# MesschieberV2.net
KiCad netlist of a schematic drawn in EAGLE
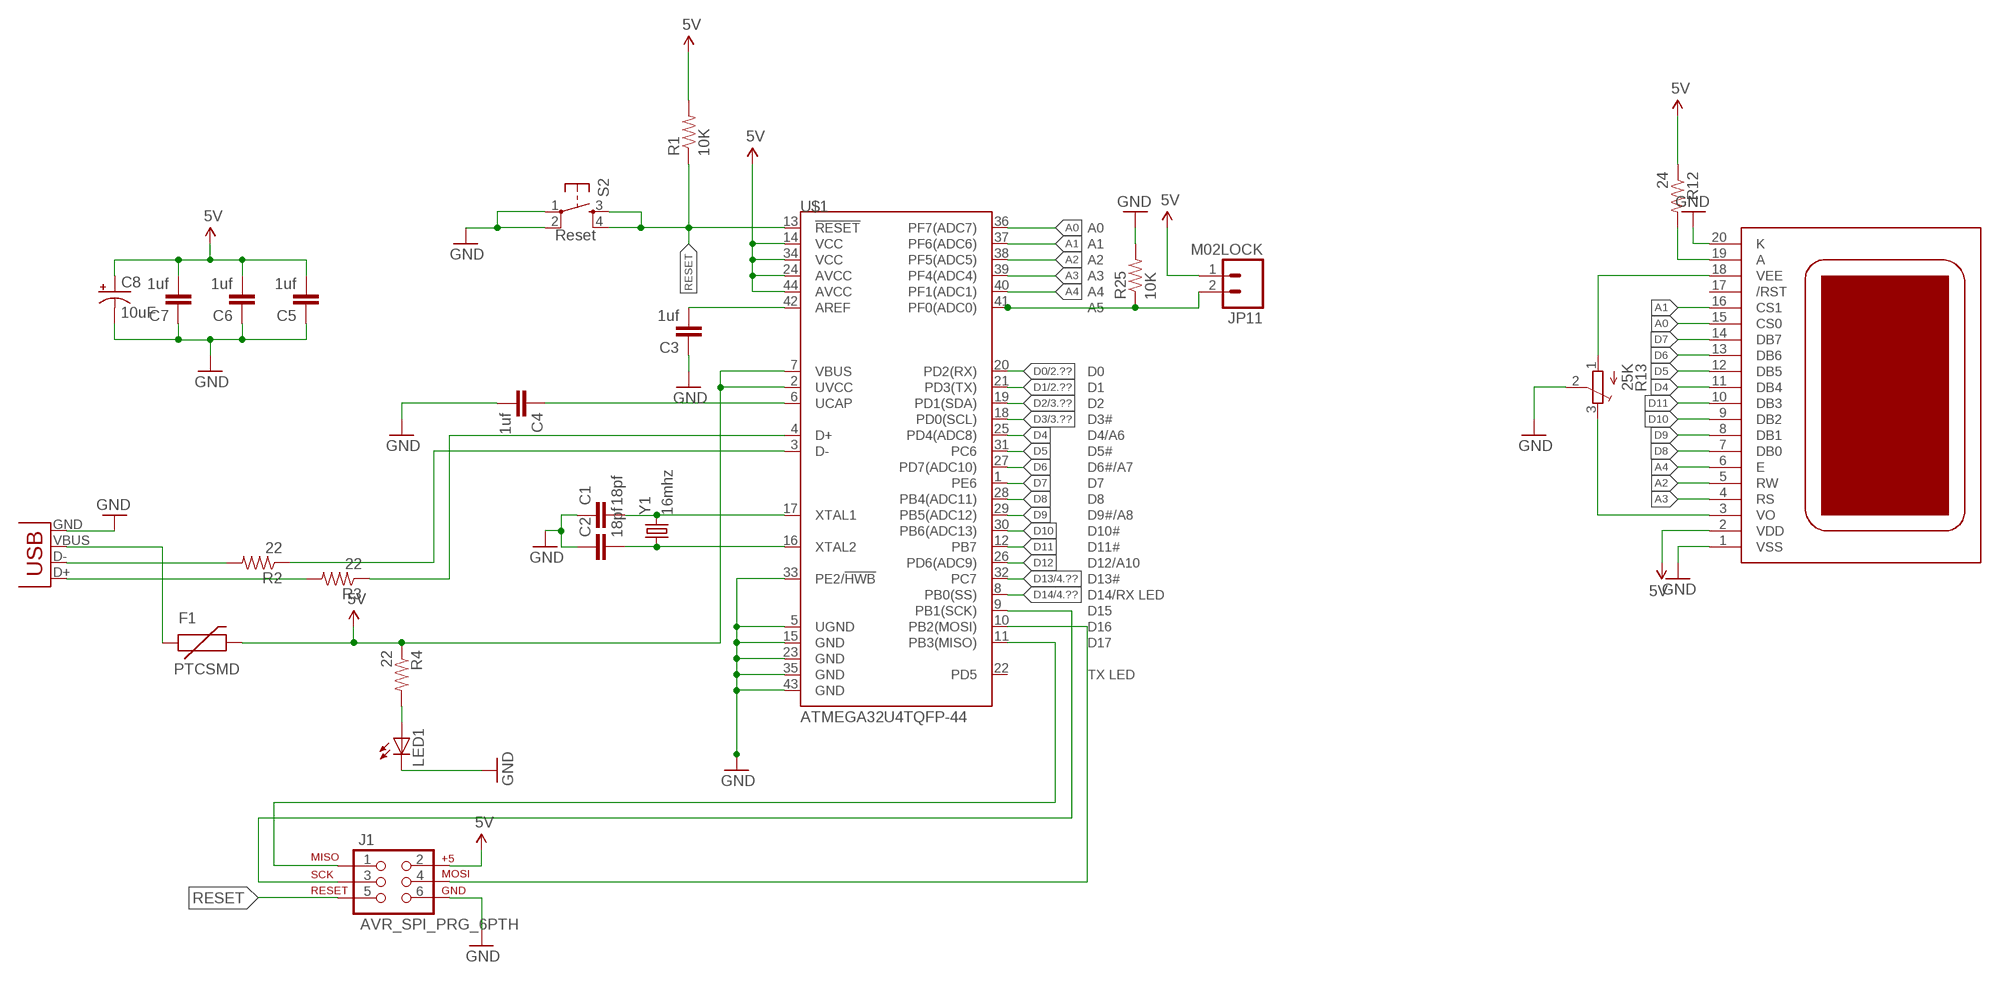
[diagram p0: schematic, sheet 1]
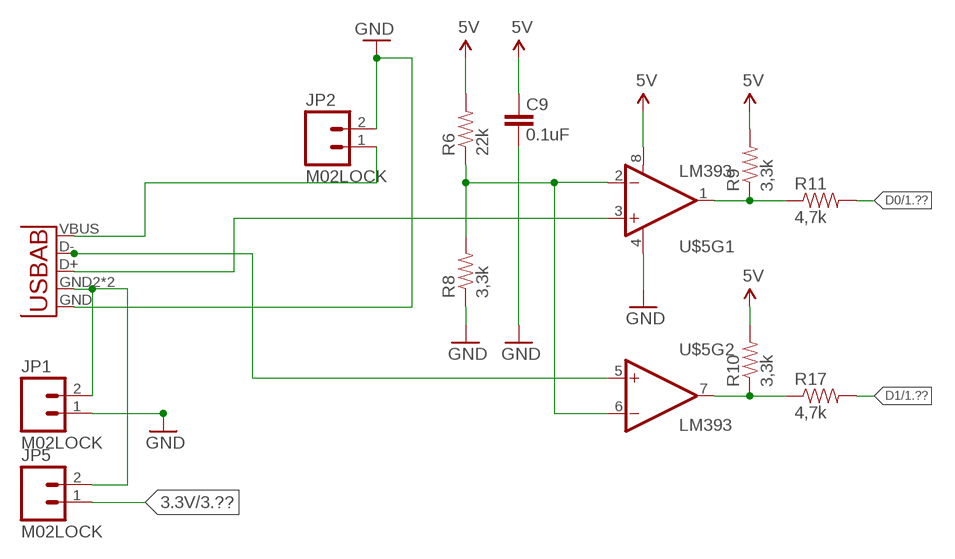
[diagram p1: schematic, sheet 2]
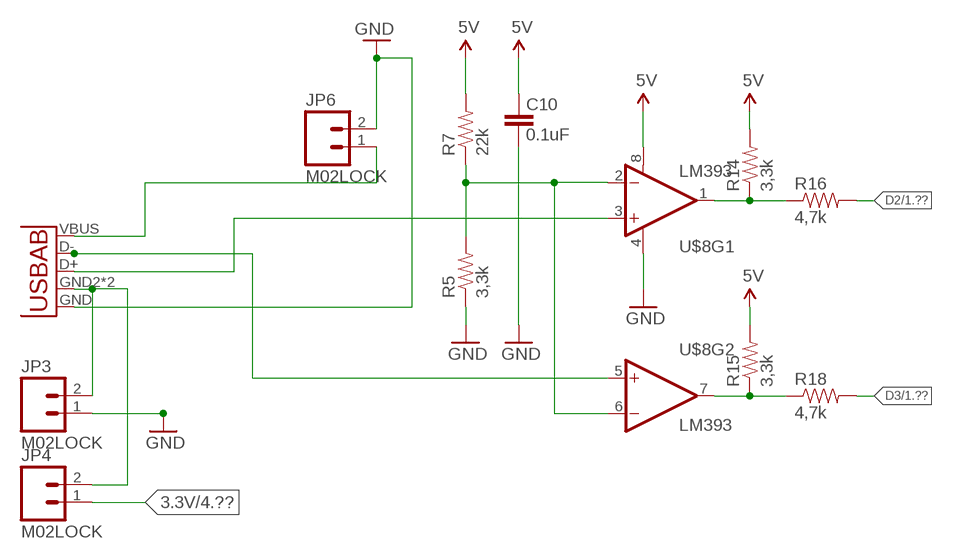
[diagram p2: schematic, sheet 3]
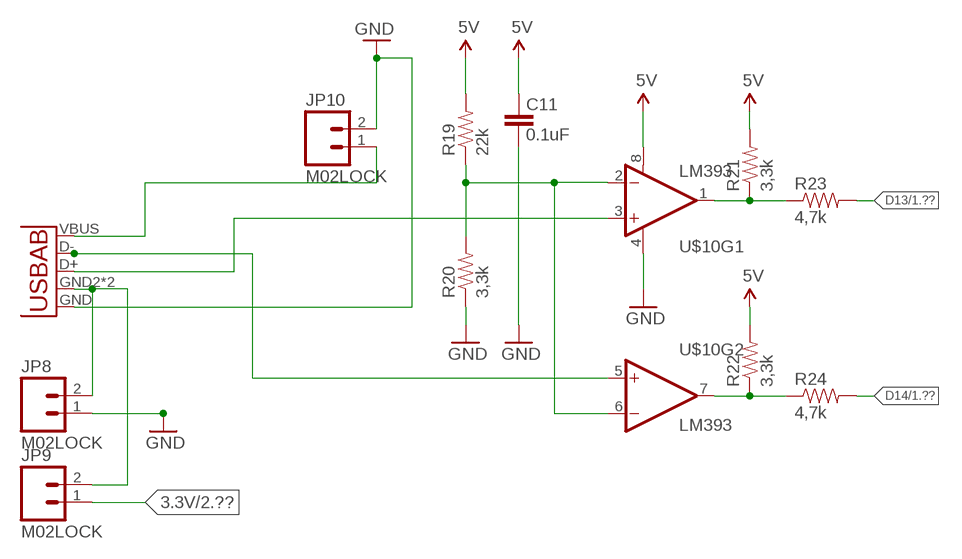
[diagram p3: schematic, sheet 4]

(export (version "E")
  (design (tool "Eeschema 10.0.6"))
  (components
    (comp (ref "C1")
      (value "18pf")
      (footprint "eagle-import:0805")
      (libsource (lib "eagle-import") (part "SparkFun-Capacitors_CAP0805"))
    )
    (comp (ref "C2")
      (value "18pf")
      (footprint "eagle-import:0805")
      (libsource (lib "eagle-import") (part "SparkFun-Capacitors_CAP0805"))
    )
    (comp (ref "C3")
      (value "1uf")
      (footprint "eagle-import:0805")
      (libsource (lib "eagle-import") (part "SparkFun-Capacitors_CAP0805"))
    )
    (comp (ref "C4")
      (value "1uf")
      (footprint "eagle-import:0805")
      (libsource (lib "eagle-import") (part "SparkFun-Capacitors_CAP0805"))
    )
    (comp (ref "C5")
      (value "1uf")
      (footprint "eagle-import:0805")
      (libsource (lib "eagle-import") (part "SparkFun-Capacitors_CAP0805"))
    )
    (comp (ref "C6")
      (value "1uf")
      (footprint "eagle-import:0805")
      (libsource (lib "eagle-import") (part "SparkFun-Capacitors_CAP0805"))
    )
    (comp (ref "C7")
      (value "1uf")
      (footprint "eagle-import:0805")
      (libsource (lib "eagle-import") (part "SparkFun-Capacitors_CAP0805"))
    )
    (comp (ref "C8")
      (value "10uF")
      (footprint "eagle-import:EIA3528")
      (libsource (lib "eagle-import") (part "10UF-20V-10%(TANT)"))
    )
    (comp (ref "F1")
      (value "PTCSMD")
      (footprint "eagle-import:PTC-1206")
      (libsource (lib "eagle-import") (part "PTCSMD"))
    )
    (comp (ref "J1")
      (value "AVR_SPI_PRG_6PTH")
      (footprint "eagle-import:2X3")
      (libsource (lib "eagle-import") (part "AVR_SPI_PRG_6PTH"))
    )
    (comp (ref "JP7")
      (value "USB-SMD-NS")
      (footprint "eagle-import:USB-MINIB-NOSTOP")
      (libsource (lib "eagle-import") (part "USB-SMD-NS"))
    )
    (comp (ref "JP11")
      (value "M02LOCK")
      (footprint "eagle-import:1X02_LOCK")
      (libsource (lib "eagle-import") (part "M02LOCK"))
    )
    (comp (ref "LED1")
      (value "LEDSML0805")
      (footprint "eagle-import:SML0805")
      (libsource (lib "eagle-import") (part "LEDSML0805"))
    )
    (comp (ref "R1")
      (value "10K")
      (footprint "eagle-import:0805")
      (libsource (lib "eagle-import") (part "RESISTOR"))
    )
    (comp (ref "R2")
      (value "22")
      (footprint "eagle-import:0805")
      (libsource (lib "eagle-import") (part "RESISTOR"))
    )
    (comp (ref "R3")
      (value "22")
      (footprint "eagle-import:0805")
      (libsource (lib "eagle-import") (part "RESISTOR"))
    )
    (comp (ref "R4")
      (value "22")
      (footprint "eagle-import:0805")
      (libsource (lib "eagle-import") (part "RESISTOR"))
    )
    (comp (ref "R12")
      (value "24")
      (footprint "eagle-import:0805")
      (libsource (lib "eagle-import") (part "RESISTOR"))
    )
    (comp (ref "R13")
      (value "25K")
      (footprint "eagle-import:SM-42_43A")
      (libsource (lib "eagle-import") (part "TRIM_EU-SM-42/43A"))
    )
    (comp (ref "R25")
      (value "10K")
      (footprint "eagle-import:0805")
      (libsource (lib "eagle-import") (part "RESISTOR"))
    )
    (comp (ref "S2")
      (value "Reset")
      (footprint "eagle-import:TACTILE_SWITCH_SMD")
      (libsource (lib "eagle-import") (part "TAC_SWITCHSND"))
    )
    (comp (ref "U$1")
      (value "ATMEGA32U4TQFP-44")
      (footprint "eagle-import:TQFP44")
      (libsource (lib "eagle-import") (part "ATMEGA32U4TQFP-44"))
    )
    (comp (ref "U$2")
      (value "TS12864A")
      (footprint "eagle-import:TS12864")
      (libsource (lib "eagle-import") (part "TS12864A"))
    )
    (comp (ref "Y1")
      (value "16mhz")
      (footprint "eagle-import:CRYSTAL-SMD-5X3")
      (libsource (lib "eagle-import") (part "CRYSTAL5X3"))
    )
    (comp (ref "C11")
      (value "0.1uF")
      (footprint "eagle-import:0805")
      (libsource (lib "eagle-import") (part "CAP0805"))
    )
    (comp (ref "JP8")
      (value "M02LOCK")
      (footprint "eagle-import:1X02_LOCK")
      (libsource (lib "eagle-import") (part "M02LOCK"))
    )
    (comp (ref "JP9")
      (value "M02LOCK")
      (footprint "eagle-import:1X02_LOCK")
      (libsource (lib "eagle-import") (part "M02LOCK"))
    )
    (comp (ref "JP10")
      (value "M02LOCK")
      (footprint "eagle-import:1X02_LOCK")
      (libsource (lib "eagle-import") (part "M02LOCK"))
    )
    (comp (ref "R19")
      (value "22k")
      (footprint "eagle-import:0805")
      (libsource (lib "eagle-import") (part "RESISTOR"))
    )
    (comp (ref "R20")
      (value "3,3k")
      (footprint "eagle-import:0805")
      (libsource (lib "eagle-import") (part "RESISTOR"))
    )
    (comp (ref "R21")
      (value "3,3k")
      (footprint "eagle-import:0805")
      (libsource (lib "eagle-import") (part "RESISTOR"))
    )
    (comp (ref "R22")
      (value "3,3k")
      (footprint "eagle-import:0805")
      (libsource (lib "eagle-import") (part "RESISTOR"))
    )
    (comp (ref "R23")
      (value "4,7k")
      (footprint "eagle-import:0805")
      (libsource (lib "eagle-import") (part "RESISTOR"))
    )
    (comp (ref "R24")
      (value "4,7k")
      (footprint "eagle-import:0805")
      (libsource (lib "eagle-import") (part "RESISTOR"))
    )
    (comp (ref "U$10")
      (value "LM393")
      (footprint "eagle-import:SO08")
      (libsource (lib "eagle-import") (part "LM393"))
    )
    (comp (ref "U$11")
      (value "USB-A")
      (footprint "eagle-import:USB-A")
      (libsource (lib "eagle-import") (part "USB-A"))
    )
    (comp (ref "C10")
      (value "0.1uF")
      (footprint "eagle-import:0805")
      (libsource (lib "eagle-import") (part "CAP0805"))
    )
    (comp (ref "JP3")
      (value "M02LOCK")
      (footprint "eagle-import:1X02_LOCK")
      (libsource (lib "eagle-import") (part "M02LOCK"))
    )
    (comp (ref "JP4")
      (value "M02LOCK")
      (footprint "eagle-import:1X02_LOCK")
      (libsource (lib "eagle-import") (part "M02LOCK"))
    )
    (comp (ref "JP6")
      (value "M02LOCK")
      (footprint "eagle-import:1X02_LOCK")
      (libsource (lib "eagle-import") (part "M02LOCK"))
    )
    (comp (ref "R5")
      (value "3,3k")
      (footprint "eagle-import:0805")
      (libsource (lib "eagle-import") (part "RESISTOR"))
    )
    (comp (ref "R7")
      (value "22k")
      (footprint "eagle-import:0805")
      (libsource (lib "eagle-import") (part "RESISTOR"))
    )
    (comp (ref "R14")
      (value "3,3k")
      (footprint "eagle-import:0805")
      (libsource (lib "eagle-import") (part "RESISTOR"))
    )
    (comp (ref "R15")
      (value "3,3k")
      (footprint "eagle-import:0805")
      (libsource (lib "eagle-import") (part "RESISTOR"))
    )
    (comp (ref "R16")
      (value "4,7k")
      (footprint "eagle-import:0805")
      (libsource (lib "eagle-import") (part "RESISTOR"))
    )
    (comp (ref "R18")
      (value "4,7k")
      (footprint "eagle-import:0805")
      (libsource (lib "eagle-import") (part "RESISTOR"))
    )
    (comp (ref "U$8")
      (value "LM393")
      (footprint "eagle-import:SO08")
      (libsource (lib "eagle-import") (part "LM393"))
    )
    (comp (ref "U$9")
      (value "USB-A")
      (footprint "eagle-import:USB-A")
      (libsource (lib "eagle-import") (part "USB-A"))
    )
    (comp (ref "C9")
      (value "0.1uF")
      (footprint "eagle-import:0805")
      (libsource (lib "eagle-import") (part "CAP0805"))
    )
    (comp (ref "JP1")
      (value "M02LOCK")
      (footprint "eagle-import:1X02_LOCK")
      (libsource (lib "eagle-import") (part "M02LOCK"))
    )
    (comp (ref "JP2")
      (value "M02LOCK")
      (footprint "eagle-import:1X02_LOCK")
      (libsource (lib "eagle-import") (part "M02LOCK"))
    )
    (comp (ref "JP5")
      (value "M02LOCK")
      (footprint "eagle-import:1X02_LOCK")
      (libsource (lib "eagle-import") (part "M02LOCK"))
    )
    (comp (ref "R6")
      (value "22k")
      (footprint "eagle-import:0805")
      (libsource (lib "eagle-import") (part "RESISTOR"))
    )
    (comp (ref "R8")
      (value "3,3k")
      (footprint "eagle-import:0805")
      (libsource (lib "eagle-import") (part "RESISTOR"))
    )
    (comp (ref "R9")
      (value "3,3k")
      (footprint "eagle-import:0805")
      (libsource (lib "eagle-import") (part "RESISTOR"))
    )
    (comp (ref "R10")
      (value "3,3k")
      (footprint "eagle-import:0805")
      (libsource (lib "eagle-import") (part "RESISTOR"))
    )
    (comp (ref "R11")
      (value "4,7k")
      (footprint "eagle-import:0805")
      (libsource (lib "eagle-import") (part "RESISTOR"))
    )
    (comp (ref "R17")
      (value "4,7k")
      (footprint "eagle-import:0805")
      (libsource (lib "eagle-import") (part "RESISTOR"))
    )
    (comp (ref "U$5")
      (value "LM393")
      (footprint "eagle-import:SO08")
      (libsource (lib "eagle-import") (part "LM393"))
    )
    (comp (ref "U$7")
      (value "USB-A")
      (footprint "eagle-import:USB-A")
      (libsource (lib "eagle-import") (part "USB-A"))
    )
  )
  (nets
    (net (code "1") (name "3.3V") (class "Default")
      (node (ref "JP4") (pin "1") (pinfunction "1_1") (pintype "passive"))
      (node (ref "JP5") (pin "1") (pinfunction "1_1") (pintype "passive"))
      (node (ref "JP9") (pin "1") (pinfunction "1_1") (pintype "passive"))
    )
    (net (code "2") (name "5V") (class "Default")
      (node (ref "C10") (pin "2") (pinfunction "2_2") (pintype "passive"))
      (node (ref "C11") (pin "2") (pinfunction "2_2") (pintype "passive"))
      (node (ref "C5") (pin "2") (pinfunction "2_2") (pintype "passive"))
      (node (ref "C6") (pin "2") (pinfunction "2_2") (pintype "passive"))
      (node (ref "C7") (pin "2") (pinfunction "2_2") (pintype "passive"))
      (node (ref "C8") (pin "A") (pinfunction "+_A") (pintype "passive"))
      (node (ref "C9") (pin "2") (pinfunction "2_2") (pintype "passive"))
      (node (ref "F1") (pin "2") (pinfunction "2_2") (pintype "bidirectional"))
      (node (ref "J1") (pin "2") (pinfunction "2_2") (pintype "passive"))
      (node (ref "JP11") (pin "1") (pinfunction "1_1") (pintype "passive"))
      (node (ref "R1") (pin "2") (pinfunction "2_2") (pintype "passive"))
      (node (ref "R10") (pin "2") (pinfunction "2_2") (pintype "passive"))
      (node (ref "R12") (pin "1") (pinfunction "1_1") (pintype "passive"))
      (node (ref "R14") (pin "2") (pinfunction "2_2") (pintype "passive"))
      (node (ref "R15") (pin "2") (pinfunction "2_2") (pintype "passive"))
      (node (ref "R19") (pin "2") (pinfunction "2_2") (pintype "passive"))
      (node (ref "R21") (pin "2") (pinfunction "2_2") (pintype "passive"))
      (node (ref "R22") (pin "2") (pinfunction "2_2") (pintype "passive"))
      (node (ref "R4") (pin "1") (pinfunction "1_1") (pintype "passive"))
      (node (ref "R6") (pin "2") (pinfunction "2_2") (pintype "passive"))
      (node (ref "R7") (pin "2") (pinfunction "2_2") (pintype "passive"))
      (node (ref "R9") (pin "2") (pinfunction "2_2") (pintype "passive"))
      (node (ref "U$1") (pin "14") (pinfunction "VCC_14") (pintype "bidirectional"))
      (node (ref "U$1") (pin "2") (pinfunction "UVCC_2") (pintype "bidirectional"))
      (node (ref "U$1") (pin "24") (pinfunction "AVCC_24") (pintype "bidirectional"))
      (node (ref "U$1") (pin "34") (pinfunction "VCC_34") (pintype "bidirectional"))
      (node (ref "U$1") (pin "44") (pinfunction "AVCC_44") (pintype "bidirectional"))
      (node (ref "U$1") (pin "7") (pinfunction "VBUS_7") (pintype "bidirectional"))
      (node (ref "U$10") (pin "8") (pinfunction "V+_8") (pintype "power_in"))
      (node (ref "U$2") (pin "2") (pinfunction "VDD_2") (pintype "power_in"))
      (node (ref "U$5") (pin "8") (pinfunction "V+_8") (pintype "power_in"))
      (node (ref "U$8") (pin "8") (pinfunction "V+_8") (pintype "power_in"))
    )
    (net (code "3") (name "A0") (class "Default")
      (node (ref "U$1") (pin "36") (pinfunction "PF7(ADC7)_36") (pintype "bidirectional"))
      (node (ref "U$2") (pin "15") (pinfunction "CS0_15") (pintype "input"))
    )
    (net (code "4") (name "A1") (class "Default")
      (node (ref "U$1") (pin "37") (pinfunction "PF6(ADC6)_37") (pintype "bidirectional"))
      (node (ref "U$2") (pin "16") (pinfunction "CS1_16") (pintype "input"))
    )
    (net (code "5") (name "A2") (class "Default")
      (node (ref "U$1") (pin "38") (pinfunction "PF5(ADC5)_38") (pintype "bidirectional"))
      (node (ref "U$2") (pin "5") (pinfunction "RW_5") (pintype "input"))
    )
    (net (code "6") (name "A3") (class "Default")
      (node (ref "U$1") (pin "39") (pinfunction "PF4(ADC4)_39") (pintype "bidirectional"))
      (node (ref "U$2") (pin "4") (pinfunction "RS_4") (pintype "input"))
    )
    (net (code "7") (name "A4") (class "Default")
      (node (ref "U$1") (pin "40") (pinfunction "PF1(ADC1)_40") (pintype "bidirectional"))
      (node (ref "U$2") (pin "6") (pinfunction "E_6") (pintype "input"))
    )
    (net (code "8") (name "D0") (class "Default")
      (node (ref "R11") (pin "2") (pinfunction "2_2") (pintype "passive"))
      (node (ref "U$1") (pin "20") (pinfunction "PD2(RX)_20") (pintype "bidirectional"))
    )
    (net (code "9") (name "D1") (class "Default")
      (node (ref "R17") (pin "2") (pinfunction "2_2") (pintype "passive"))
      (node (ref "U$1") (pin "21") (pinfunction "PD3(TX)_21") (pintype "bidirectional"))
    )
    (net (code "10") (name "D2") (class "Default")
      (node (ref "R16") (pin "2") (pinfunction "2_2") (pintype "passive"))
      (node (ref "U$1") (pin "19") (pinfunction "PD1(SDA)_19") (pintype "bidirectional"))
    )
    (net (code "11") (name "D3") (class "Default")
      (node (ref "R18") (pin "2") (pinfunction "2_2") (pintype "passive"))
      (node (ref "U$1") (pin "18") (pinfunction "PD0(SCL)_18") (pintype "bidirectional"))
    )
    (net (code "12") (name "D4") (class "Default")
      (node (ref "U$1") (pin "25") (pinfunction "PD4(ADC8)_25") (pintype "bidirectional"))
      (node (ref "U$2") (pin "11") (pinfunction "DB4_11") (pintype "bidirectional"))
    )
    (net (code "13") (name "D5") (class "Default")
      (node (ref "U$1") (pin "31") (pinfunction "PC6_31") (pintype "bidirectional"))
      (node (ref "U$2") (pin "12") (pinfunction "DB5_12") (pintype "bidirectional"))
    )
    (net (code "14") (name "D6") (class "Default")
      (node (ref "U$1") (pin "27") (pinfunction "PD7(ADC10)_27") (pintype "bidirectional"))
      (node (ref "U$2") (pin "13") (pinfunction "DB6_13") (pintype "bidirectional"))
    )
    (net (code "15") (name "D7") (class "Default")
      (node (ref "U$1") (pin "1") (pinfunction "PE6_1") (pintype "bidirectional"))
      (node (ref "U$2") (pin "14") (pinfunction "DB7_14") (pintype "bidirectional"))
    )
    (net (code "16") (name "D8") (class "Default")
      (node (ref "U$1") (pin "28") (pinfunction "PB4(ADC11)_28") (pintype "bidirectional"))
      (node (ref "U$2") (pin "7") (pinfunction "DB0_7") (pintype "bidirectional"))
    )
    (net (code "17") (name "D9") (class "Default")
      (node (ref "U$1") (pin "29") (pinfunction "PB5(ADC12)_29") (pintype "bidirectional"))
      (node (ref "U$2") (pin "8") (pinfunction "DB1_8") (pintype "bidirectional"))
    )
    (net (code "18") (name "D10") (class "Default")
      (node (ref "U$1") (pin "30") (pinfunction "PB6(ADC13)_30") (pintype "bidirectional"))
      (node (ref "U$2") (pin "9") (pinfunction "DB2_9") (pintype "bidirectional"))
    )
    (net (code "19") (name "D11") (class "Default")
      (node (ref "U$1") (pin "12") (pinfunction "PB7_12") (pintype "bidirectional"))
      (node (ref "U$2") (pin "10") (pinfunction "DB3_10") (pintype "bidirectional"))
    )
    (net (code "20") (name "D12") (class "Default")
      (node (ref "U$1") (pin "26") (pinfunction "PD6(ADC9)_26") (pintype "bidirectional"))
    )
    (net (code "21") (name "D13") (class "Default")
      (node (ref "R23") (pin "2") (pinfunction "2_2") (pintype "passive"))
      (node (ref "U$1") (pin "32") (pinfunction "PC7_32") (pintype "bidirectional"))
    )
    (net (code "22") (name "D14") (class "Default")
      (node (ref "R24") (pin "2") (pinfunction "2_2") (pintype "passive"))
      (node (ref "U$1") (pin "8") (pinfunction "PB0(SS)_8") (pintype "bidirectional"))
    )
    (net (code "23") (name "GND") (class "Default")
      (node (ref "C1") (pin "1") (pinfunction "1_1") (pintype "passive"))
      (node (ref "C10") (pin "1") (pinfunction "1_1") (pintype "passive"))
      (node (ref "C11") (pin "1") (pinfunction "1_1") (pintype "passive"))
      (node (ref "C2") (pin "1") (pinfunction "1_1") (pintype "passive"))
      (node (ref "C3") (pin "1") (pinfunction "1_1") (pintype "passive"))
      (node (ref "C4") (pin "2") (pinfunction "2_2") (pintype "passive"))
      (node (ref "C5") (pin "1") (pinfunction "1_1") (pintype "passive"))
      (node (ref "C6") (pin "1") (pinfunction "1_1") (pintype "passive"))
      (node (ref "C7") (pin "1") (pinfunction "1_1") (pintype "passive"))
      (node (ref "C8") (pin "C") (pinfunction "-_C") (pintype "passive"))
      (node (ref "C9") (pin "1") (pinfunction "1_1") (pintype "passive"))
      (node (ref "J1") (pin "6") (pinfunction "6_6") (pintype "passive"))
      (node (ref "JP1") (pin "1") (pinfunction "1_1") (pintype "passive"))
      (node (ref "JP10") (pin "2") (pinfunction "2_2") (pintype "passive"))
      (node (ref "JP2") (pin "2") (pinfunction "2_2") (pintype "passive"))
      (node (ref "JP3") (pin "1") (pinfunction "1_1") (pintype "passive"))
      (node (ref "JP6") (pin "2") (pinfunction "2_2") (pintype "passive"))
      (node (ref "JP7") (pin "GND") (pinfunction "GND_GND") (pintype "bidirectional"))
      (node (ref "JP8") (pin "1") (pinfunction "1_1") (pintype "passive"))
      (node (ref "LED1") (pin "C") (pinfunction "C_C") (pintype "passive"))
      (node (ref "R13") (pin "2") (pinfunction "S_2") (pintype "passive"))
      (node (ref "R20") (pin "1") (pinfunction "1_1") (pintype "passive"))
      (node (ref "R25") (pin "2") (pinfunction "2_2") (pintype "passive"))
      (node (ref "R5") (pin "1") (pinfunction "1_1") (pintype "passive"))
      (node (ref "R8") (pin "1") (pinfunction "1_1") (pintype "passive"))
      (node (ref "S2") (pin "1") (pinfunction "1_1") (pintype "passive"))
      (node (ref "S2") (pin "2") (pinfunction "2_2") (pintype "passive"))
      (node (ref "U$1") (pin "15") (pinfunction "GND_15") (pintype "bidirectional"))
      (node (ref "U$1") (pin "23") (pinfunction "GND_23") (pintype "bidirectional"))
      (node (ref "U$1") (pin "33") (pinfunction "PE2/~{HWB}_33") (pintype "bidirectional"))
      (node (ref "U$1") (pin "35") (pinfunction "GND_35") (pintype "bidirectional"))
      (node (ref "U$1") (pin "43") (pinfunction "GND_43") (pintype "bidirectional"))
      (node (ref "U$1") (pin "5") (pinfunction "UGND_5") (pintype "bidirectional"))
      (node (ref "U$10") (pin "4") (pinfunction "V-_4") (pintype "power_in"))
      (node (ref "U$11") (pin "GND") (pinfunction "GND_GND") (pintype "bidirectional"))
      (node (ref "U$2") (pin "1") (pinfunction "VSS_1") (pintype "power_in"))
      (node (ref "U$2") (pin "20") (pinfunction "K_20") (pintype "input"))
      (node (ref "U$5") (pin "4") (pinfunction "V-_4") (pintype "power_in"))
      (node (ref "U$7") (pin "GND") (pinfunction "GND_GND") (pintype "bidirectional"))
      (node (ref "U$8") (pin "4") (pinfunction "V-_4") (pintype "power_in"))
      (node (ref "U$9") (pin "GND") (pinfunction "GND_GND") (pintype "bidirectional"))
    )
    (net (code "24") (name "Net-(F1-Pad1)") (class "Default")
      (node (ref "F1") (pin "1") (pinfunction "1_1") (pintype "bidirectional"))
      (node (ref "JP7") (pin "VBUS") (pinfunction "VBUS_VBUS") (pintype "bidirectional"))
    )
    (net (code "25") (name "Net-(JP1-Pad2)") (class "Default")
      (node (ref "JP1") (pin "2") (pinfunction "2_2") (pintype "passive"))
      (node (ref "JP5") (pin "2") (pinfunction "2_2") (pintype "passive"))
      (node (ref "U$7") (pin "GND2") (pinfunction "USBID_GND2") (pintype "bidirectional"))
      (node (ref "U$7") (pin "GND3") (pinfunction "USBID_GND3") (pintype "bidirectional"))
    )
    (net (code "26") (name "Net-(JP2-Pad1)") (class "Default")
      (node (ref "JP2") (pin "1") (pinfunction "1_1") (pintype "passive"))
      (node (ref "U$7") (pin "VBUS") (pinfunction "VBUS_VBUS") (pintype "bidirectional"))
    )
    (net (code "27") (name "Net-(JP3-Pad2)") (class "Default")
      (node (ref "JP3") (pin "2") (pinfunction "2_2") (pintype "passive"))
      (node (ref "JP4") (pin "2") (pinfunction "2_2") (pintype "passive"))
      (node (ref "U$9") (pin "GND2") (pinfunction "USBID_GND2") (pintype "bidirectional"))
      (node (ref "U$9") (pin "GND3") (pinfunction "USBID_GND3") (pintype "bidirectional"))
    )
    (net (code "28") (name "Net-(JP6-Pad1)") (class "Default")
      (node (ref "JP6") (pin "1") (pinfunction "1_1") (pintype "passive"))
      (node (ref "U$9") (pin "VBUS") (pinfunction "VBUS_VBUS") (pintype "bidirectional"))
    )
    (net (code "29") (name "Net-(JP7-PadD+)") (class "Default")
      (node (ref "JP7") (pin "D+") (pinfunction "D+_D+") (pintype "bidirectional"))
      (node (ref "R3") (pin "2") (pinfunction "2_2") (pintype "passive"))
    )
    (net (code "30") (name "Net-(JP7-PadD-)") (class "Default")
      (node (ref "JP7") (pin "D-") (pinfunction "D-_D-") (pintype "bidirectional"))
      (node (ref "R2") (pin "2") (pinfunction "2_2") (pintype "passive"))
    )
    (net (code "31") (name "Net-(JP8-Pad2)") (class "Default")
      (node (ref "JP8") (pin "2") (pinfunction "2_2") (pintype "passive"))
      (node (ref "JP9") (pin "2") (pinfunction "2_2") (pintype "passive"))
      (node (ref "U$11") (pin "GND2") (pinfunction "USBID_GND2") (pintype "bidirectional"))
      (node (ref "U$11") (pin "GND3") (pinfunction "USBID_GND3") (pintype "bidirectional"))
    )
    (net (code "32") (name "Net-(JP10-Pad1)") (class "Default")
      (node (ref "JP10") (pin "1") (pinfunction "1_1") (pintype "passive"))
      (node (ref "U$11") (pin "VBUS") (pinfunction "VBUS_VBUS") (pintype "bidirectional"))
    )
    (net (code "33") (name "Net-(LED1-PadA)") (class "Default")
      (node (ref "LED1") (pin "A") (pinfunction "A_A") (pintype "passive"))
      (node (ref "R4") (pin "2") (pinfunction "2_2") (pintype "passive"))
    )
    (net (code "34") (name "Net-(R13-A)") (class "Default")
      (node (ref "R13") (pin "1") (pinfunction "A_1") (pintype "passive"))
      (node (ref "U$2") (pin "18") (pinfunction "VEE_18") (pintype "power_in"))
    )
    (net (code "35") (name "Net-(R13-E)") (class "Default")
      (node (ref "R13") (pin "3") (pinfunction "E_3") (pintype "passive"))
      (node (ref "U$2") (pin "3") (pinfunction "VO_3") (pintype "input"))
    )
    (net (code "36") (name "Net-(U$1-AREF)") (class "Default")
      (node (ref "C3") (pin "2") (pinfunction "2_2") (pintype "passive"))
      (node (ref "U$1") (pin "42") (pinfunction "AREF_42") (pintype "bidirectional"))
    )
    (net (code "37") (name "Net-(U$1-D+)") (class "Default")
      (node (ref "R3") (pin "1") (pinfunction "1_1") (pintype "passive"))
      (node (ref "U$1") (pin "4") (pinfunction "D+_4") (pintype "bidirectional"))
    )
    (net (code "38") (name "Net-(U$1-D-)") (class "Default")
      (node (ref "R2") (pin "1") (pinfunction "1_1") (pintype "passive"))
      (node (ref "U$1") (pin "3") (pinfunction "D-_3") (pintype "bidirectional"))
    )
    (net (code "39") (name "Net-(U$1-PB1(SCK))") (class "Default")
      (node (ref "J1") (pin "3") (pinfunction "3_3") (pintype "passive"))
      (node (ref "U$1") (pin "9") (pinfunction "PB1(SCK)_9") (pintype "bidirectional"))
    )
    (net (code "40") (name "Net-(U$1-PB2(MOSI))") (class "Default")
      (node (ref "J1") (pin "4") (pinfunction "4_4") (pintype "passive"))
      (node (ref "U$1") (pin "10") (pinfunction "PB2(MOSI)_10") (pintype "bidirectional"))
    )
    (net (code "41") (name "Net-(U$1-PB3(MISO))") (class "Default")
      (node (ref "J1") (pin "1") (pinfunction "1_1") (pintype "passive"))
      (node (ref "U$1") (pin "11") (pinfunction "PB3(MISO)_11") (pintype "bidirectional"))
    )
    (net (code "42") (name "Net-(U$1-PF0(ADC0))") (class "Default")
      (node (ref "JP11") (pin "2") (pinfunction "2_2") (pintype "passive"))
      (node (ref "R25") (pin "1") (pinfunction "1_1") (pintype "passive"))
      (node (ref "U$1") (pin "41") (pinfunction "PF0(ADC0)_41") (pintype "bidirectional"))
    )
    (net (code "43") (name "Net-(U$1-UCAP)") (class "Default")
      (node (ref "C4") (pin "1") (pinfunction "1_1") (pintype "passive"))
      (node (ref "U$1") (pin "6") (pinfunction "UCAP_6") (pintype "bidirectional"))
    )
    (net (code "44") (name "Net-(U$1-XTAL1)") (class "Default")
      (node (ref "C1") (pin "2") (pinfunction "2_2") (pintype "passive"))
      (node (ref "U$1") (pin "17") (pinfunction "XTAL1_17") (pintype "bidirectional"))
      (node (ref "Y1") (pin "3") (pinfunction "2_3") (pintype "passive"))
    )
    (net (code "45") (name "Net-(U$1-XTAL2)") (class "Default")
      (node (ref "C2") (pin "2") (pinfunction "2_2") (pintype "passive"))
      (node (ref "U$1") (pin "16") (pinfunction "XTAL2_16") (pintype "bidirectional"))
      (node (ref "Y1") (pin "1") (pinfunction "1_1") (pintype "passive"))
    )
    (net (code "46") (name "Net-(U$2-A)") (class "Default")
      (node (ref "R12") (pin "2") (pinfunction "2_2") (pintype "passive"))
      (node (ref "U$2") (pin "19") (pinfunction "A_19") (pintype "power_in"))
    )
    (net (code "47") (name "Net-(U$5A-+IN)") (class "Default")
      (node (ref "U$5") (pin "3") (pinfunction "+IN_3") (pintype "input"))
      (node (ref "U$7") (pin "D+") (pinfunction "D+_D+") (pintype "bidirectional"))
    )
    (net (code "48") (name "Net-(U$5A--IN)") (class "Default")
      (node (ref "R6") (pin "1") (pinfunction "1_1") (pintype "passive"))
      (node (ref "R8") (pin "2") (pinfunction "2_2") (pintype "passive"))
      (node (ref "U$5") (pin "2") (pinfunction "-IN_2") (pintype "input"))
      (node (ref "U$5") (pin "6") (pinfunction "-IN_6") (pintype "input"))
    )
    (net (code "49") (name "Net-(U$5A-OUT)") (class "Default")
      (node (ref "R11") (pin "1") (pinfunction "1_1") (pintype "passive"))
      (node (ref "R9") (pin "1") (pinfunction "1_1") (pintype "passive"))
      (node (ref "U$5") (pin "1") (pinfunction "OUT_1") (pintype "output"))
    )
    (net (code "50") (name "Net-(U$5B-+IN)") (class "Default")
      (node (ref "U$5") (pin "5") (pinfunction "+IN_5") (pintype "input"))
      (node (ref "U$7") (pin "D-") (pinfunction "D-_D-") (pintype "bidirectional"))
    )
    (net (code "51") (name "Net-(U$5B-OUT)") (class "Default")
      (node (ref "R10") (pin "1") (pinfunction "1_1") (pintype "passive"))
      (node (ref "R17") (pin "1") (pinfunction "1_1") (pintype "passive"))
      (node (ref "U$5") (pin "7") (pinfunction "OUT_7") (pintype "output"))
    )
    (net (code "52") (name "Net-(U$8A-+IN)") (class "Default")
      (node (ref "U$8") (pin "3") (pinfunction "+IN_3") (pintype "input"))
      (node (ref "U$9") (pin "D+") (pinfunction "D+_D+") (pintype "bidirectional"))
    )
    (net (code "53") (name "Net-(U$8A--IN)") (class "Default")
      (node (ref "R5") (pin "2") (pinfunction "2_2") (pintype "passive"))
      (node (ref "R7") (pin "1") (pinfunction "1_1") (pintype "passive"))
      (node (ref "U$8") (pin "2") (pinfunction "-IN_2") (pintype "input"))
      (node (ref "U$8") (pin "6") (pinfunction "-IN_6") (pintype "input"))
    )
    (net (code "54") (name "Net-(U$8A-OUT)") (class "Default")
      (node (ref "R14") (pin "1") (pinfunction "1_1") (pintype "passive"))
      (node (ref "R16") (pin "1") (pinfunction "1_1") (pintype "passive"))
      (node (ref "U$8") (pin "1") (pinfunction "OUT_1") (pintype "output"))
    )
    (net (code "55") (name "Net-(U$8B-+IN)") (class "Default")
      (node (ref "U$8") (pin "5") (pinfunction "+IN_5") (pintype "input"))
      (node (ref "U$9") (pin "D-") (pinfunction "D-_D-") (pintype "bidirectional"))
    )
    (net (code "56") (name "Net-(U$8B-OUT)") (class "Default")
      (node (ref "R15") (pin "1") (pinfunction "1_1") (pintype "passive"))
      (node (ref "R18") (pin "1") (pinfunction "1_1") (pintype "passive"))
      (node (ref "U$8") (pin "7") (pinfunction "OUT_7") (pintype "output"))
    )
    (net (code "57") (name "Net-(U$10A-+IN)") (class "Default")
      (node (ref "U$10") (pin "3") (pinfunction "+IN_3") (pintype "input"))
      (node (ref "U$11") (pin "D+") (pinfunction "D+_D+") (pintype "bidirectional"))
    )
    (net (code "58") (name "Net-(U$10A--IN)") (class "Default")
      (node (ref "R19") (pin "1") (pinfunction "1_1") (pintype "passive"))
      (node (ref "R20") (pin "2") (pinfunction "2_2") (pintype "passive"))
      (node (ref "U$10") (pin "2") (pinfunction "-IN_2") (pintype "input"))
      (node (ref "U$10") (pin "6") (pinfunction "-IN_6") (pintype "input"))
    )
    (net (code "59") (name "Net-(U$10A-OUT)") (class "Default")
      (node (ref "R21") (pin "1") (pinfunction "1_1") (pintype "passive"))
      (node (ref "R23") (pin "1") (pinfunction "1_1") (pintype "passive"))
      (node (ref "U$10") (pin "1") (pinfunction "OUT_1") (pintype "output"))
    )
    (net (code "60") (name "Net-(U$10B-+IN)") (class "Default")
      (node (ref "U$10") (pin "5") (pinfunction "+IN_5") (pintype "input"))
      (node (ref "U$11") (pin "D-") (pinfunction "D-_D-") (pintype "bidirectional"))
    )
    (net (code "61") (name "Net-(U$10B-OUT)") (class "Default")
      (node (ref "R22") (pin "1") (pinfunction "1_1") (pintype "passive"))
      (node (ref "R24") (pin "1") (pinfunction "1_1") (pintype "passive"))
      (node (ref "U$10") (pin "7") (pinfunction "OUT_7") (pintype "output"))
    )
    (net (code "62") (name "RESET") (class "Default")
      (node (ref "J1") (pin "5") (pinfunction "5_5") (pintype "passive"))
      (node (ref "R1") (pin "1") (pinfunction "1_1") (pintype "passive"))
      (node (ref "S2") (pin "3") (pinfunction "3_3") (pintype "passive"))
      (node (ref "S2") (pin "4") (pinfunction "4_4") (pintype "passive"))
      (node (ref "U$1") (pin "13") (pinfunction "~{RESET}_13") (pintype "bidirectional"))
    )
    (net (code "63") (name "unconnected-(U$1-PD5-Pad22)") (class "Default")
      (node (ref "U$1") (pin "22") (pinfunction "PD5_22") (pintype "bidirectional"))
    )
    (net (code "64") (name "unconnected-(U$2-{slash}RST-Pad17)") (class "Default")
      (node (ref "U$2") (pin "17") (pinfunction "/RST_17") (pintype "input"))
    )
  )
)
